# isstracker.net
KiCad netlist of a schematic drawn in EAGLE
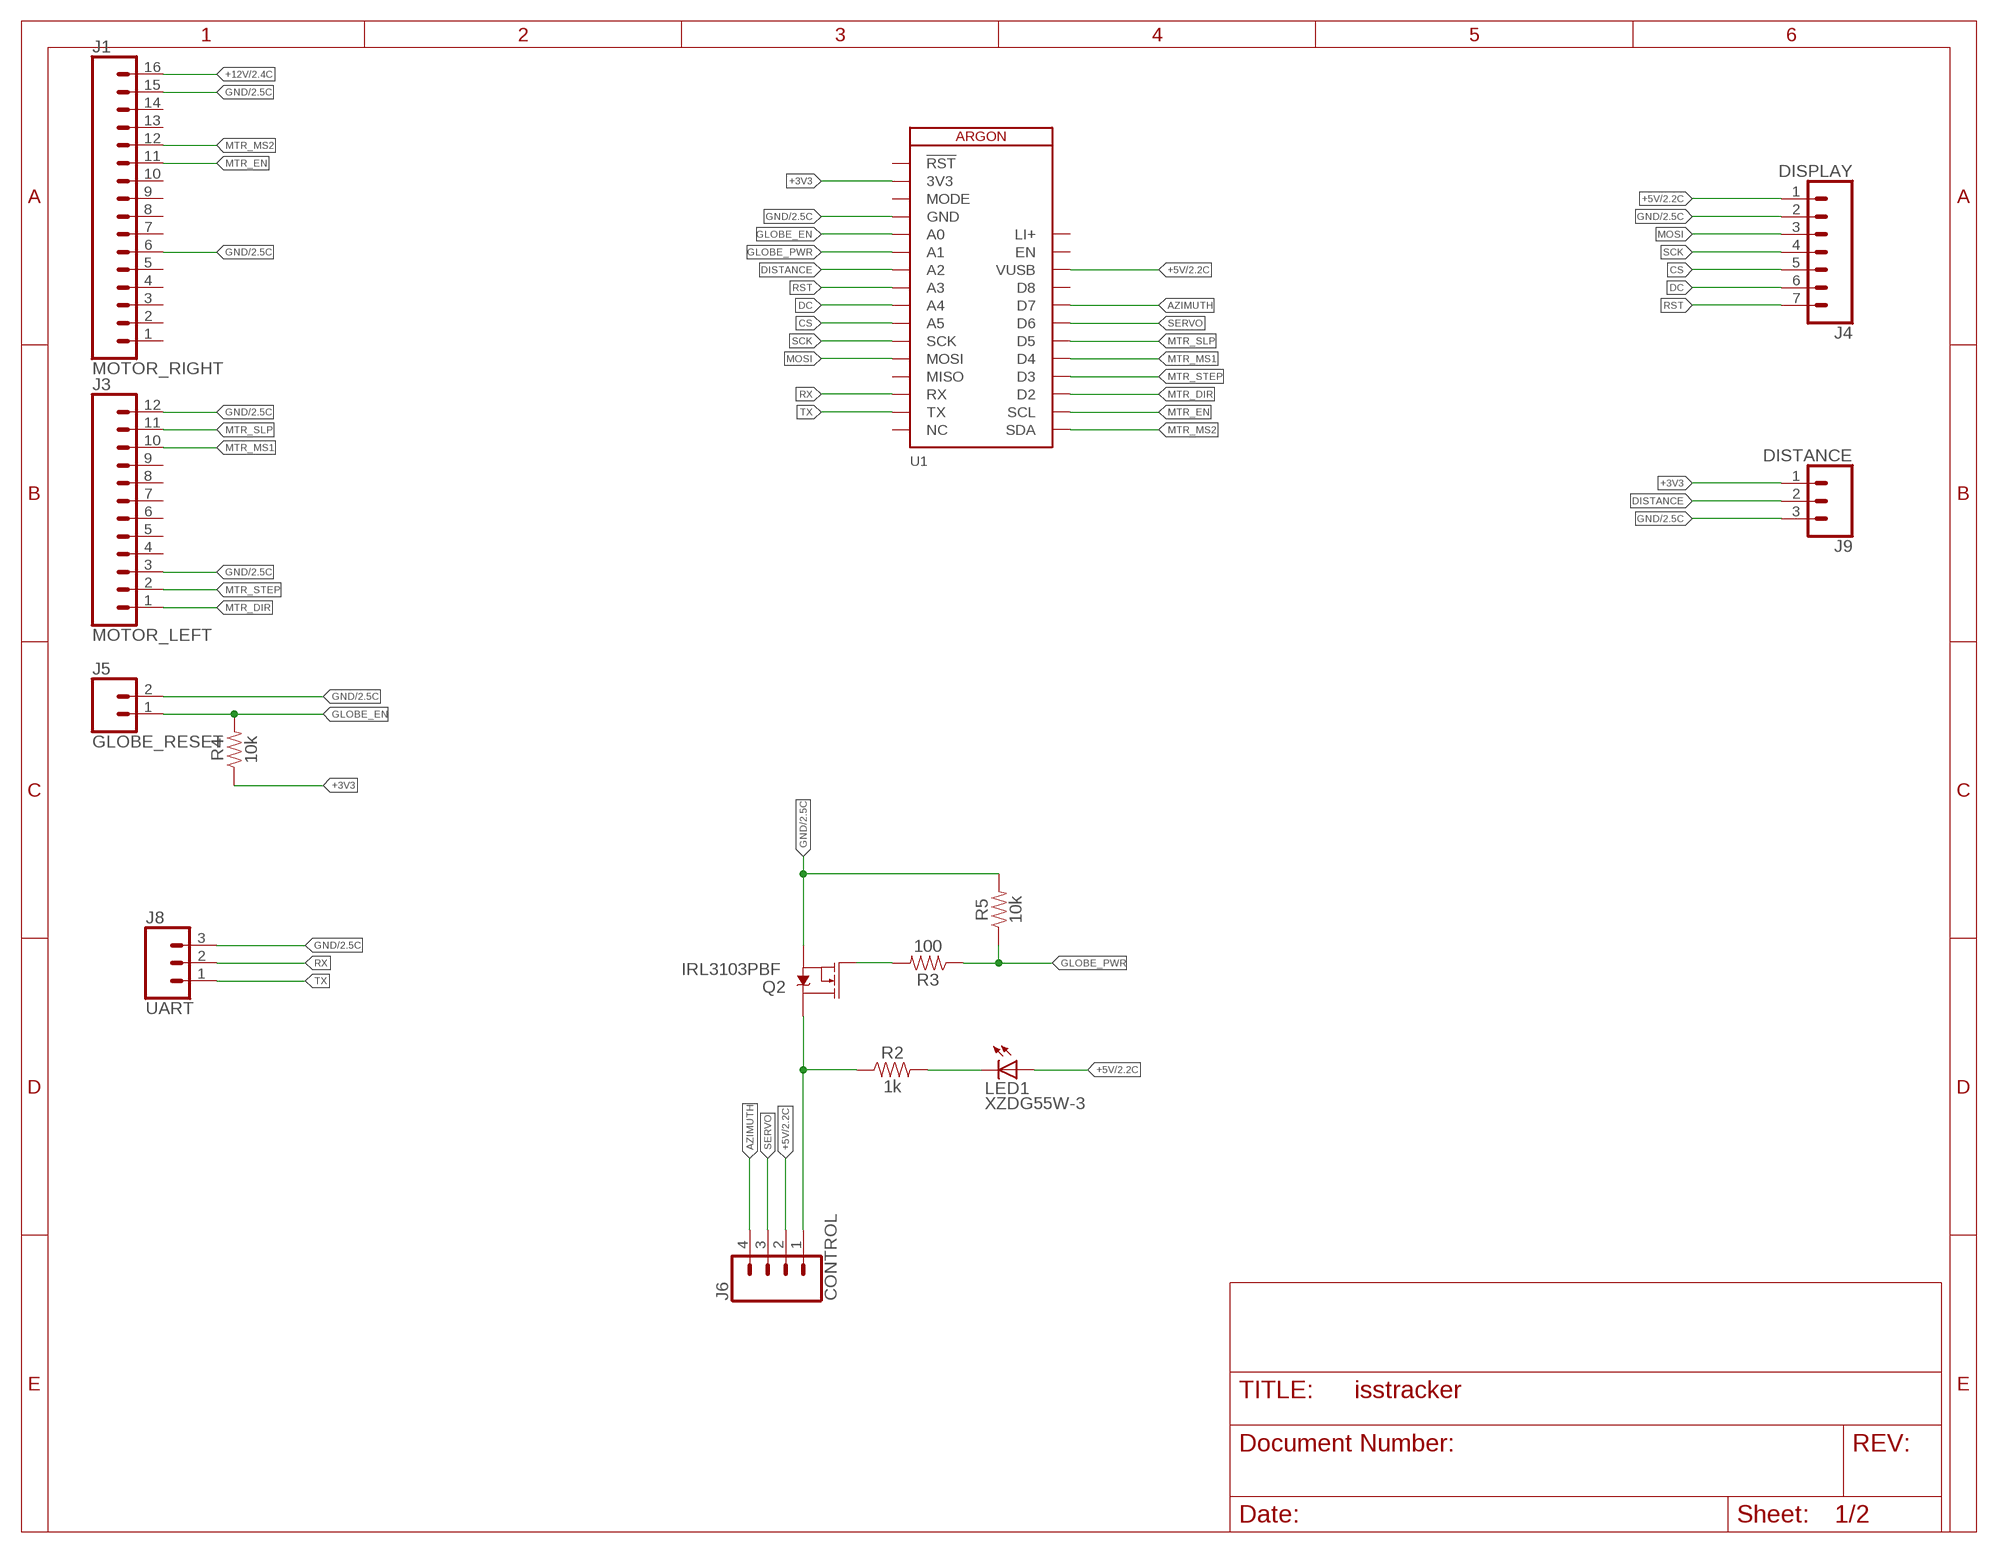
[diagram p0: schematic, sheet 1]
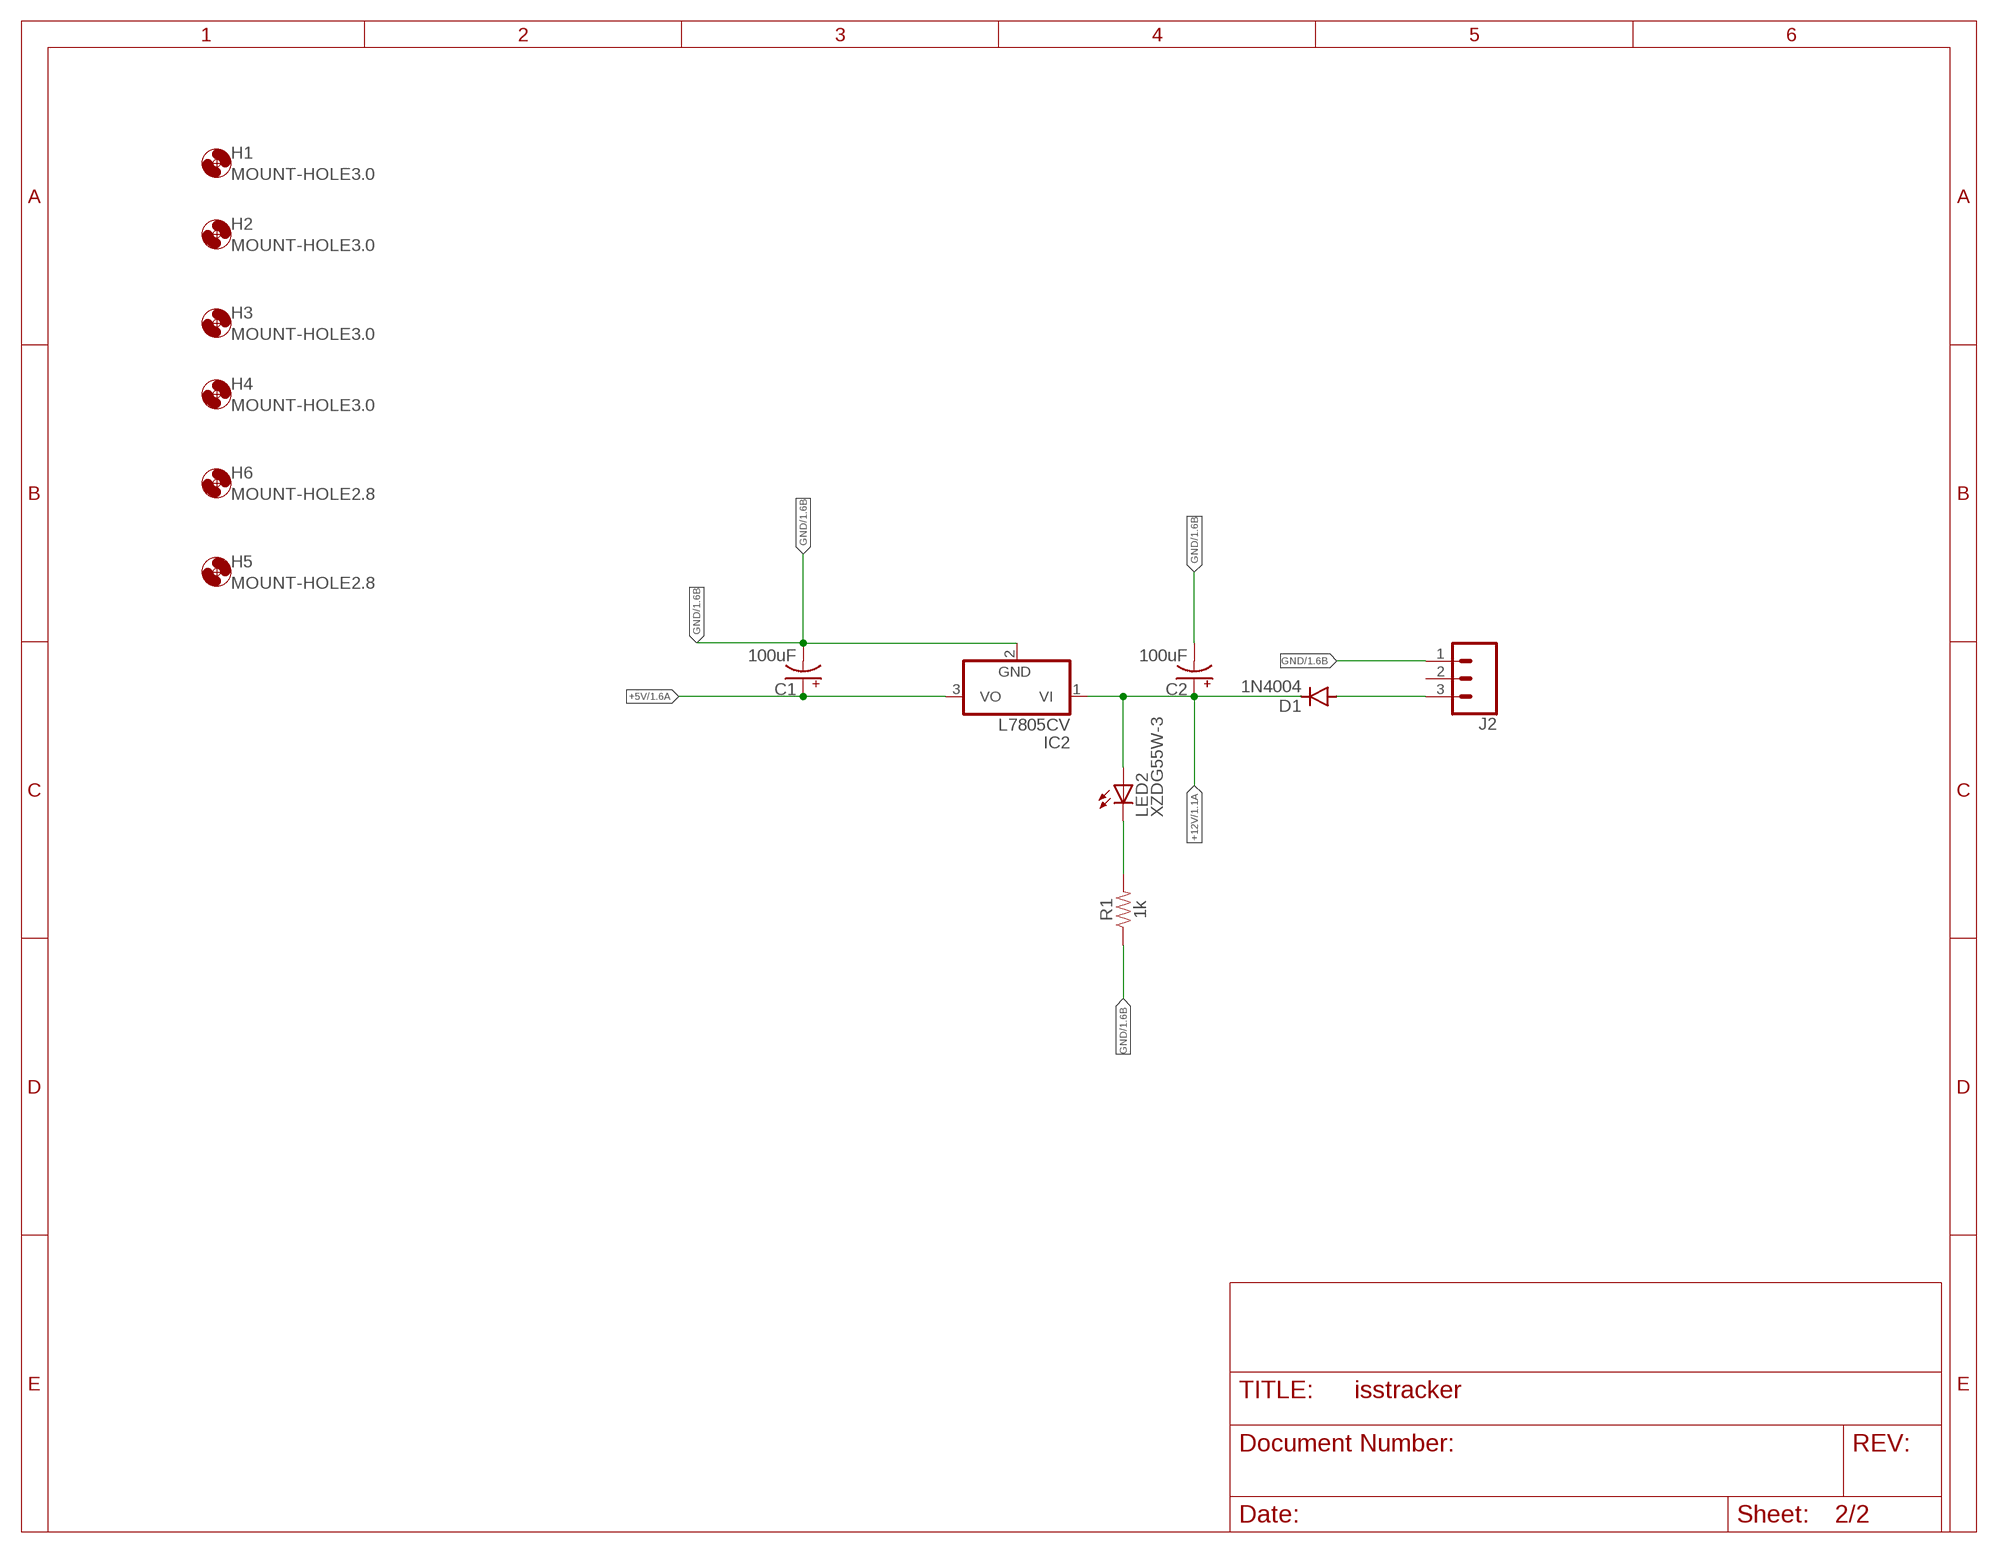
[diagram p1: schematic, sheet 2]

(export (version "E")
  (design (tool "Eeschema 10.0.6"))
  (components
    (comp (ref "C1")
      (value "100uF")
      (footprint "eagle-import:CPOL-RADIAL-2.5MM-6.5MM")
      (libsource (lib "eagle-import") (part "100UF-POLAR-RADIAL-2.5MM-25V-20%"))
    )
    (comp (ref "C2")
      (value "100uF")
      (footprint "eagle-import:CPOL-RADIAL-2.5MM-6.5MM")
      (libsource (lib "eagle-import") (part "100UF-POLAR-RADIAL-2.5MM-25V-20%"))
    )
    (comp (ref "D1")
      (value "1N4004")
      (footprint "eagle-import:DO41-10")
      (libsource (lib "eagle-import") (part "1N4004"))
    )
    (comp (ref "H1")
      (value "MOUNT-HOLE3.0")
      (footprint "eagle-import:3,0")
      (libsource (lib "eagle-import") (part "MOUNT-HOLE3.0"))
    )
    (comp (ref "H2")
      (value "MOUNT-HOLE3.0")
      (footprint "eagle-import:3,0")
      (libsource (lib "eagle-import") (part "MOUNT-HOLE3.0"))
    )
    (comp (ref "H3")
      (value "MOUNT-HOLE3.0")
      (footprint "eagle-import:3,0")
      (libsource (lib "eagle-import") (part "MOUNT-HOLE3.0"))
    )
    (comp (ref "H4")
      (value "MOUNT-HOLE3.0")
      (footprint "eagle-import:3,0")
      (libsource (lib "eagle-import") (part "MOUNT-HOLE3.0"))
    )
    (comp (ref "H5")
      (value "MOUNT-HOLE2.8")
      (footprint "eagle-import:2,8")
      (libsource (lib "eagle-import") (part "MOUNT-HOLE2.8"))
    )
    (comp (ref "H6")
      (value "MOUNT-HOLE2.8")
      (footprint "eagle-import:2,8")
      (libsource (lib "eagle-import") (part "MOUNT-HOLE2.8"))
    )
    (comp (ref "IC2")
      (value "L7805CV")
      (footprint "eagle-import:TO220V")
      (libsource (lib "eagle-import") (part "78TV05"))
    )
    (comp (ref "J2")
      (value "CONN_03LOCK_LONGPADS")
      (footprint "eagle-import:1X03_LOCK_LONGPADS")
      (libsource (lib "eagle-import") (part "CONN_03LOCK_LONGPADS"))
    )
    (comp (ref "LED2")
      (value "XZDG55W-3")
      (footprint "eagle-import:CHIPLED_1206")
      (libsource (lib "eagle-import") (part "LEDCHIPLED_1206"))
    )
    (comp (ref "R1")
      (value "1k")
      (footprint "eagle-import:0805")
      (libsource (lib "eagle-import") (part "0.3OHM-0805-1/8W-1%"))
    )
    (comp (ref "J1")
      (value "MOTOR_RIGHT")
      (footprint "eagle-import:1X16")
      (libsource (lib "eagle-import") (part "CONN_16"))
    )
    (comp (ref "J3")
      (value "MOTOR_LEFT")
      (footprint "eagle-import:1X12")
      (libsource (lib "eagle-import") (part "CONN_12"))
    )
    (comp (ref "J4")
      (value "DISPLAY")
      (footprint "eagle-import:1X07")
      (libsource (lib "eagle-import") (part "CONN_07"))
    )
    (comp (ref "J5")
      (value "GLOBE_RESET")
      (footprint "eagle-import:1X02")
      (libsource (lib "eagle-import") (part "CONN_02"))
    )
    (comp (ref "J6")
      (value "CONTROL")
      (footprint "eagle-import:1X04")
      (libsource (lib "eagle-import") (part "CONN_04"))
    )
    (comp (ref "J8")
      (value "UART")
      (footprint "eagle-import:1X03")
      (libsource (lib "eagle-import") (part "CONN_03"))
    )
    (comp (ref "J9")
      (value "DISTANCE")
      (footprint "eagle-import:1X03")
      (libsource (lib "eagle-import") (part "CONN_03"))
    )
    (comp (ref "LED1")
      (value "XZDG55W-3")
      (footprint "eagle-import:CHIPLED_1206")
      (libsource (lib "eagle-import") (part "LEDCHIPLED_1206"))
    )
    (comp (ref "Q2")
      (value "IRL3103PBF")
      (footprint "eagle-import:TO220V")
      (libsource (lib "eagle-import") (part "MOSFET-NCH-FQP30N06L"))
    )
    (comp (ref "R2")
      (value "1k")
      (footprint "eagle-import:0805")
      (libsource (lib "eagle-import") (part "0.75OHM-0805-1/4W-1%"))
    )
    (comp (ref "R3")
      (value "100")
      (footprint "eagle-import:0805")
      (libsource (lib "eagle-import") (part "0.75OHM-0805-1/4W-1%"))
    )
    (comp (ref "R4")
      (value "10k")
      (footprint "eagle-import:0805")
      (libsource (lib "eagle-import") (part "0.75OHM-0805-1/4W-1%"))
    )
    (comp (ref "R5")
      (value "10k")
      (footprint "eagle-import:0805")
      (libsource (lib "eagle-import") (part "0.75OHM-0805-1/4W-1%"))
    )
    (comp (ref "U1")
      (value "ARGON")
      (footprint "eagle-import:ARGON")
      (libsource (lib "eagle-import") (part "ARGON"))
    )
  )
  (nets
    (net (code "1") (name "+3V3") (class "Default")
      (node (ref "J9") (pin "1") (pinfunction "1_1") (pintype "passive"))
      (node (ref "R4") (pin "1") (pinfunction "1_1") (pintype "passive"))
      (node (ref "U1") (pin "2") (pinfunction "3V3_2") (pintype "power_in"))
    )
    (net (code "2") (name "+5V") (class "Default")
      (node (ref "C1") (pin "1") (pinfunction "+_1") (pintype "passive"))
      (node (ref "IC2") (pin "3") (pinfunction "VO_3") (pintype "passive"))
      (node (ref "J4") (pin "1") (pinfunction "1_1") (pintype "passive"))
      (node (ref "J6") (pin "2") (pinfunction "2_2") (pintype "passive"))
      (node (ref "LED1") (pin "A") (pinfunction "A_A") (pintype "passive"))
      (node (ref "U1") (pin "26") (pinfunction "VUSB_26") (pintype "power_in"))
    )
    (net (code "3") (name "+12V") (class "Default")
      (node (ref "C2") (pin "1") (pinfunction "+_1") (pintype "passive"))
      (node (ref "D1") (pin "C") (pinfunction "C_C") (pintype "passive"))
      (node (ref "IC2") (pin "1") (pinfunction "VI_1") (pintype "input"))
      (node (ref "J1") (pin "16") (pinfunction "16_16") (pintype "passive"))
      (node (ref "LED2") (pin "A") (pinfunction "A_A") (pintype "passive"))
    )
    (net (code "4") (name "AZIMUTH") (class "Default")
      (node (ref "J6") (pin "4") (pinfunction "4_4") (pintype "passive"))
      (node (ref "U1") (pin "24") (pinfunction "D7_24") (pintype "bidirectional"))
    )
    (net (code "5") (name "CS") (class "Default")
      (node (ref "J4") (pin "5") (pinfunction "5_5") (pintype "passive"))
      (node (ref "U1") (pin "10") (pinfunction "A5_10") (pintype "bidirectional"))
    )
    (net (code "6") (name "DC") (class "Default")
      (node (ref "J4") (pin "6") (pinfunction "6_6") (pintype "passive"))
      (node (ref "U1") (pin "9") (pinfunction "A4_9") (pintype "bidirectional"))
    )
    (net (code "7") (name "DISTANCE") (class "Default")
      (node (ref "J9") (pin "2") (pinfunction "2_2") (pintype "passive"))
      (node (ref "U1") (pin "7") (pinfunction "A2_7") (pintype "bidirectional"))
    )
    (net (code "8") (name "GLOBE_EN") (class "Default")
      (node (ref "J5") (pin "1") (pinfunction "1_1") (pintype "passive"))
      (node (ref "R4") (pin "2") (pinfunction "2_2") (pintype "passive"))
      (node (ref "U1") (pin "5") (pinfunction "A0_5") (pintype "bidirectional"))
    )
    (net (code "9") (name "GLOBE_PWR") (class "Default")
      (node (ref "R3") (pin "1") (pinfunction "1_1") (pintype "passive"))
      (node (ref "R5") (pin "1") (pinfunction "1_1") (pintype "passive"))
      (node (ref "U1") (pin "6") (pinfunction "A1_6") (pintype "bidirectional"))
    )
    (net (code "10") (name "GND") (class "Default")
      (node (ref "C1") (pin "2") (pinfunction "-_2") (pintype "passive"))
      (node (ref "C2") (pin "2") (pinfunction "-_2") (pintype "passive"))
      (node (ref "IC2") (pin "2") (pinfunction "GND_2") (pintype "passive"))
      (node (ref "J1") (pin "15") (pinfunction "15_15") (pintype "passive"))
      (node (ref "J1") (pin "6") (pinfunction "6_6") (pintype "passive"))
      (node (ref "J2") (pin "1") (pinfunction "1_1") (pintype "passive"))
      (node (ref "J3") (pin "12") (pinfunction "12_12") (pintype "passive"))
      (node (ref "J3") (pin "3") (pinfunction "3_3") (pintype "passive"))
      (node (ref "J4") (pin "2") (pinfunction "2_2") (pintype "passive"))
      (node (ref "J5") (pin "2") (pinfunction "2_2") (pintype "passive"))
      (node (ref "J8") (pin "3") (pinfunction "3_3") (pintype "passive"))
      (node (ref "J9") (pin "3") (pinfunction "3_3") (pintype "passive"))
      (node (ref "Q2") (pin "3") (pinfunction "S_3") (pintype "bidirectional"))
      (node (ref "R1") (pin "1") (pinfunction "1_1") (pintype "passive"))
      (node (ref "R5") (pin "2") (pinfunction "2_2") (pintype "passive"))
      (node (ref "U1") (pin "4") (pinfunction "GND_4") (pintype "power_in"))
    )
    (net (code "11") (name "LI+") (class "Default")
      (node (ref "U1") (pin "28") (pinfunction "LI+_28") (pintype "power_in"))
    )
    (net (code "12") (name "MOSI") (class "Default")
      (node (ref "J4") (pin "3") (pinfunction "3_3") (pintype "passive"))
      (node (ref "U1") (pin "12") (pinfunction "MOSI_12") (pintype "bidirectional"))
    )
    (net (code "13") (name "MTR_DIR") (class "Default")
      (node (ref "J3") (pin "1") (pinfunction "1_1") (pintype "passive"))
      (node (ref "U1") (pin "19") (pinfunction "D2_19") (pintype "bidirectional"))
    )
    (net (code "14") (name "MTR_EN") (class "Default")
      (node (ref "J1") (pin "11") (pinfunction "11_11") (pintype "passive"))
      (node (ref "U1") (pin "18") (pinfunction "SCL_18") (pintype "bidirectional"))
    )
    (net (code "15") (name "MTR_MS1") (class "Default")
      (node (ref "J3") (pin "10") (pinfunction "10_10") (pintype "passive"))
      (node (ref "U1") (pin "21") (pinfunction "D4_21") (pintype "bidirectional"))
    )
    (net (code "16") (name "MTR_MS2") (class "Default")
      (node (ref "J1") (pin "12") (pinfunction "12_12") (pintype "passive"))
      (node (ref "U1") (pin "17") (pinfunction "SDA_17") (pintype "bidirectional"))
    )
    (net (code "17") (name "MTR_SLP") (class "Default")
      (node (ref "J3") (pin "11") (pinfunction "11_11") (pintype "passive"))
      (node (ref "U1") (pin "22") (pinfunction "D5_22") (pintype "bidirectional"))
    )
    (net (code "18") (name "MTR_STEP") (class "Default")
      (node (ref "J3") (pin "2") (pinfunction "2_2") (pintype "passive"))
      (node (ref "U1") (pin "20") (pinfunction "D3_20") (pintype "bidirectional"))
    )
    (net (code "19") (name "Net-(D1-PadA)") (class "Default")
      (node (ref "D1") (pin "A") (pinfunction "A_A") (pintype "passive"))
      (node (ref "J2") (pin "3") (pinfunction "3_3") (pintype "passive"))
    )
    (net (code "20") (name "Net-(LED1-PadC)") (class "Default")
      (node (ref "LED1") (pin "C") (pinfunction "C_C") (pintype "passive"))
      (node (ref "R2") (pin "2") (pinfunction "2_2") (pintype "passive"))
    )
    (net (code "21") (name "Net-(LED2-PadC)") (class "Default")
      (node (ref "LED2") (pin "C") (pinfunction "C_C") (pintype "passive"))
      (node (ref "R1") (pin "2") (pinfunction "2_2") (pintype "passive"))
    )
    (net (code "22") (name "Net-(Q2-D)") (class "Default")
      (node (ref "J6") (pin "1") (pinfunction "1_1") (pintype "passive"))
      (node (ref "Q2") (pin "2") (pinfunction "D_2") (pintype "bidirectional"))
      (node (ref "R2") (pin "1") (pinfunction "1_1") (pintype "passive"))
    )
    (net (code "23") (name "Net-(Q2-G)") (class "Default")
      (node (ref "Q2") (pin "1") (pinfunction "G_1") (pintype "bidirectional"))
      (node (ref "R3") (pin "2") (pinfunction "2_2") (pintype "passive"))
    )
    (net (code "24") (name "RST") (class "Default")
      (node (ref "J4") (pin "7") (pinfunction "7_7") (pintype "passive"))
      (node (ref "U1") (pin "8") (pinfunction "A3_8") (pintype "bidirectional"))
    )
    (net (code "25") (name "RX") (class "Default")
      (node (ref "J8") (pin "2") (pinfunction "2_2") (pintype "passive"))
      (node (ref "U1") (pin "14") (pinfunction "RX_14") (pintype "bidirectional"))
    )
    (net (code "26") (name "SCK") (class "Default")
      (node (ref "J4") (pin "4") (pinfunction "4_4") (pintype "passive"))
      (node (ref "U1") (pin "11") (pinfunction "SCK_11") (pintype "bidirectional"))
    )
    (net (code "27") (name "SERVO") (class "Default")
      (node (ref "J6") (pin "3") (pinfunction "3_3") (pintype "passive"))
      (node (ref "U1") (pin "23") (pinfunction "D6_23") (pintype "bidirectional"))
    )
    (net (code "28") (name "TX") (class "Default")
      (node (ref "J8") (pin "1") (pinfunction "1_1") (pintype "passive"))
      (node (ref "U1") (pin "15") (pinfunction "TX_15") (pintype "bidirectional"))
    )
    (net (code "29") (name "unconnected-(J1-Pad1)") (class "Default")
      (node (ref "J1") (pin "1") (pinfunction "1_1") (pintype "passive"))
    )
    (net (code "30") (name "unconnected-(J1-Pad2)") (class "Default")
      (node (ref "J1") (pin "2") (pinfunction "2_2") (pintype "passive"))
    )
    (net (code "31") (name "unconnected-(J1-Pad3)") (class "Default")
      (node (ref "J1") (pin "3") (pinfunction "3_3") (pintype "passive"))
    )
    (net (code "32") (name "unconnected-(J1-Pad4)") (class "Default")
      (node (ref "J1") (pin "4") (pinfunction "4_4") (pintype "passive"))
    )
    (net (code "33") (name "unconnected-(J1-Pad5)") (class "Default")
      (node (ref "J1") (pin "5") (pinfunction "5_5") (pintype "passive"))
    )
    (net (code "34") (name "unconnected-(J1-Pad7)") (class "Default")
      (node (ref "J1") (pin "7") (pinfunction "7_7") (pintype "passive"))
    )
    (net (code "35") (name "unconnected-(J1-Pad8)") (class "Default")
      (node (ref "J1") (pin "8") (pinfunction "8_8") (pintype "passive"))
    )
    (net (code "36") (name "unconnected-(J1-Pad9)") (class "Default")
      (node (ref "J1") (pin "9") (pinfunction "9_9") (pintype "passive"))
    )
    (net (code "37") (name "unconnected-(J1-Pad10)") (class "Default")
      (node (ref "J1") (pin "10") (pinfunction "10_10") (pintype "passive"))
    )
    (net (code "38") (name "unconnected-(J1-Pad13)") (class "Default")
      (node (ref "J1") (pin "13") (pinfunction "13_13") (pintype "passive"))
    )
    (net (code "39") (name "unconnected-(J1-Pad14)") (class "Default")
      (node (ref "J1") (pin "14") (pinfunction "14_14") (pintype "passive"))
    )
    (net (code "40") (name "unconnected-(J2-Pad2)") (class "Default")
      (node (ref "J2") (pin "2") (pinfunction "2_2") (pintype "passive"))
    )
    (net (code "41") (name "unconnected-(J3-Pad4)") (class "Default")
      (node (ref "J3") (pin "4") (pinfunction "4_4") (pintype "passive"))
    )
    (net (code "42") (name "unconnected-(J3-Pad5)") (class "Default")
      (node (ref "J3") (pin "5") (pinfunction "5_5") (pintype "passive"))
    )
    (net (code "43") (name "unconnected-(J3-Pad6)") (class "Default")
      (node (ref "J3") (pin "6") (pinfunction "6_6") (pintype "passive"))
    )
    (net (code "44") (name "unconnected-(J3-Pad7)") (class "Default")
      (node (ref "J3") (pin "7") (pinfunction "7_7") (pintype "passive"))
    )
    (net (code "45") (name "unconnected-(J3-Pad8)") (class "Default")
      (node (ref "J3") (pin "8") (pinfunction "8_8") (pintype "passive"))
    )
    (net (code "46") (name "unconnected-(J3-Pad9)") (class "Default")
      (node (ref "J3") (pin "9") (pinfunction "9_9") (pintype "passive"))
    )
    (net (code "47") (name "unconnected-(U1-D8-Pad25)") (class "Default")
      (node (ref "U1") (pin "25") (pinfunction "D8_25") (pintype "bidirectional"))
    )
    (net (code "48") (name "unconnected-(U1-EN-Pad27)") (class "Default")
      (node (ref "U1") (pin "27") (pinfunction "EN_27") (pintype "input"))
    )
    (net (code "49") (name "unconnected-(U1-MISO-Pad13)") (class "Default")
      (node (ref "U1") (pin "13") (pinfunction "MISO_13") (pintype "bidirectional"))
    )
    (net (code "50") (name "unconnected-(U1-MODE-Pad3)") (class "Default")
      (node (ref "U1") (pin "3") (pinfunction "MODE_3") (pintype "bidirectional"))
    )
    (net (code "51") (name "unconnected-(U1-NC-Pad16)") (class "Default")
      (node (ref "U1") (pin "16") (pinfunction "NC_16") (pintype "bidirectional"))
    )
    (net (code "52") (name "unconnected-(U1-~{RST}-Pad1)") (class "Default")
      (node (ref "U1") (pin "1") (pinfunction "~{RST}_1") (pintype "input"))
    )
  )
)
